# SCH_RFID-design_2024-09-27.net
KiCad netlist of a schematic drawn in EasyEDA
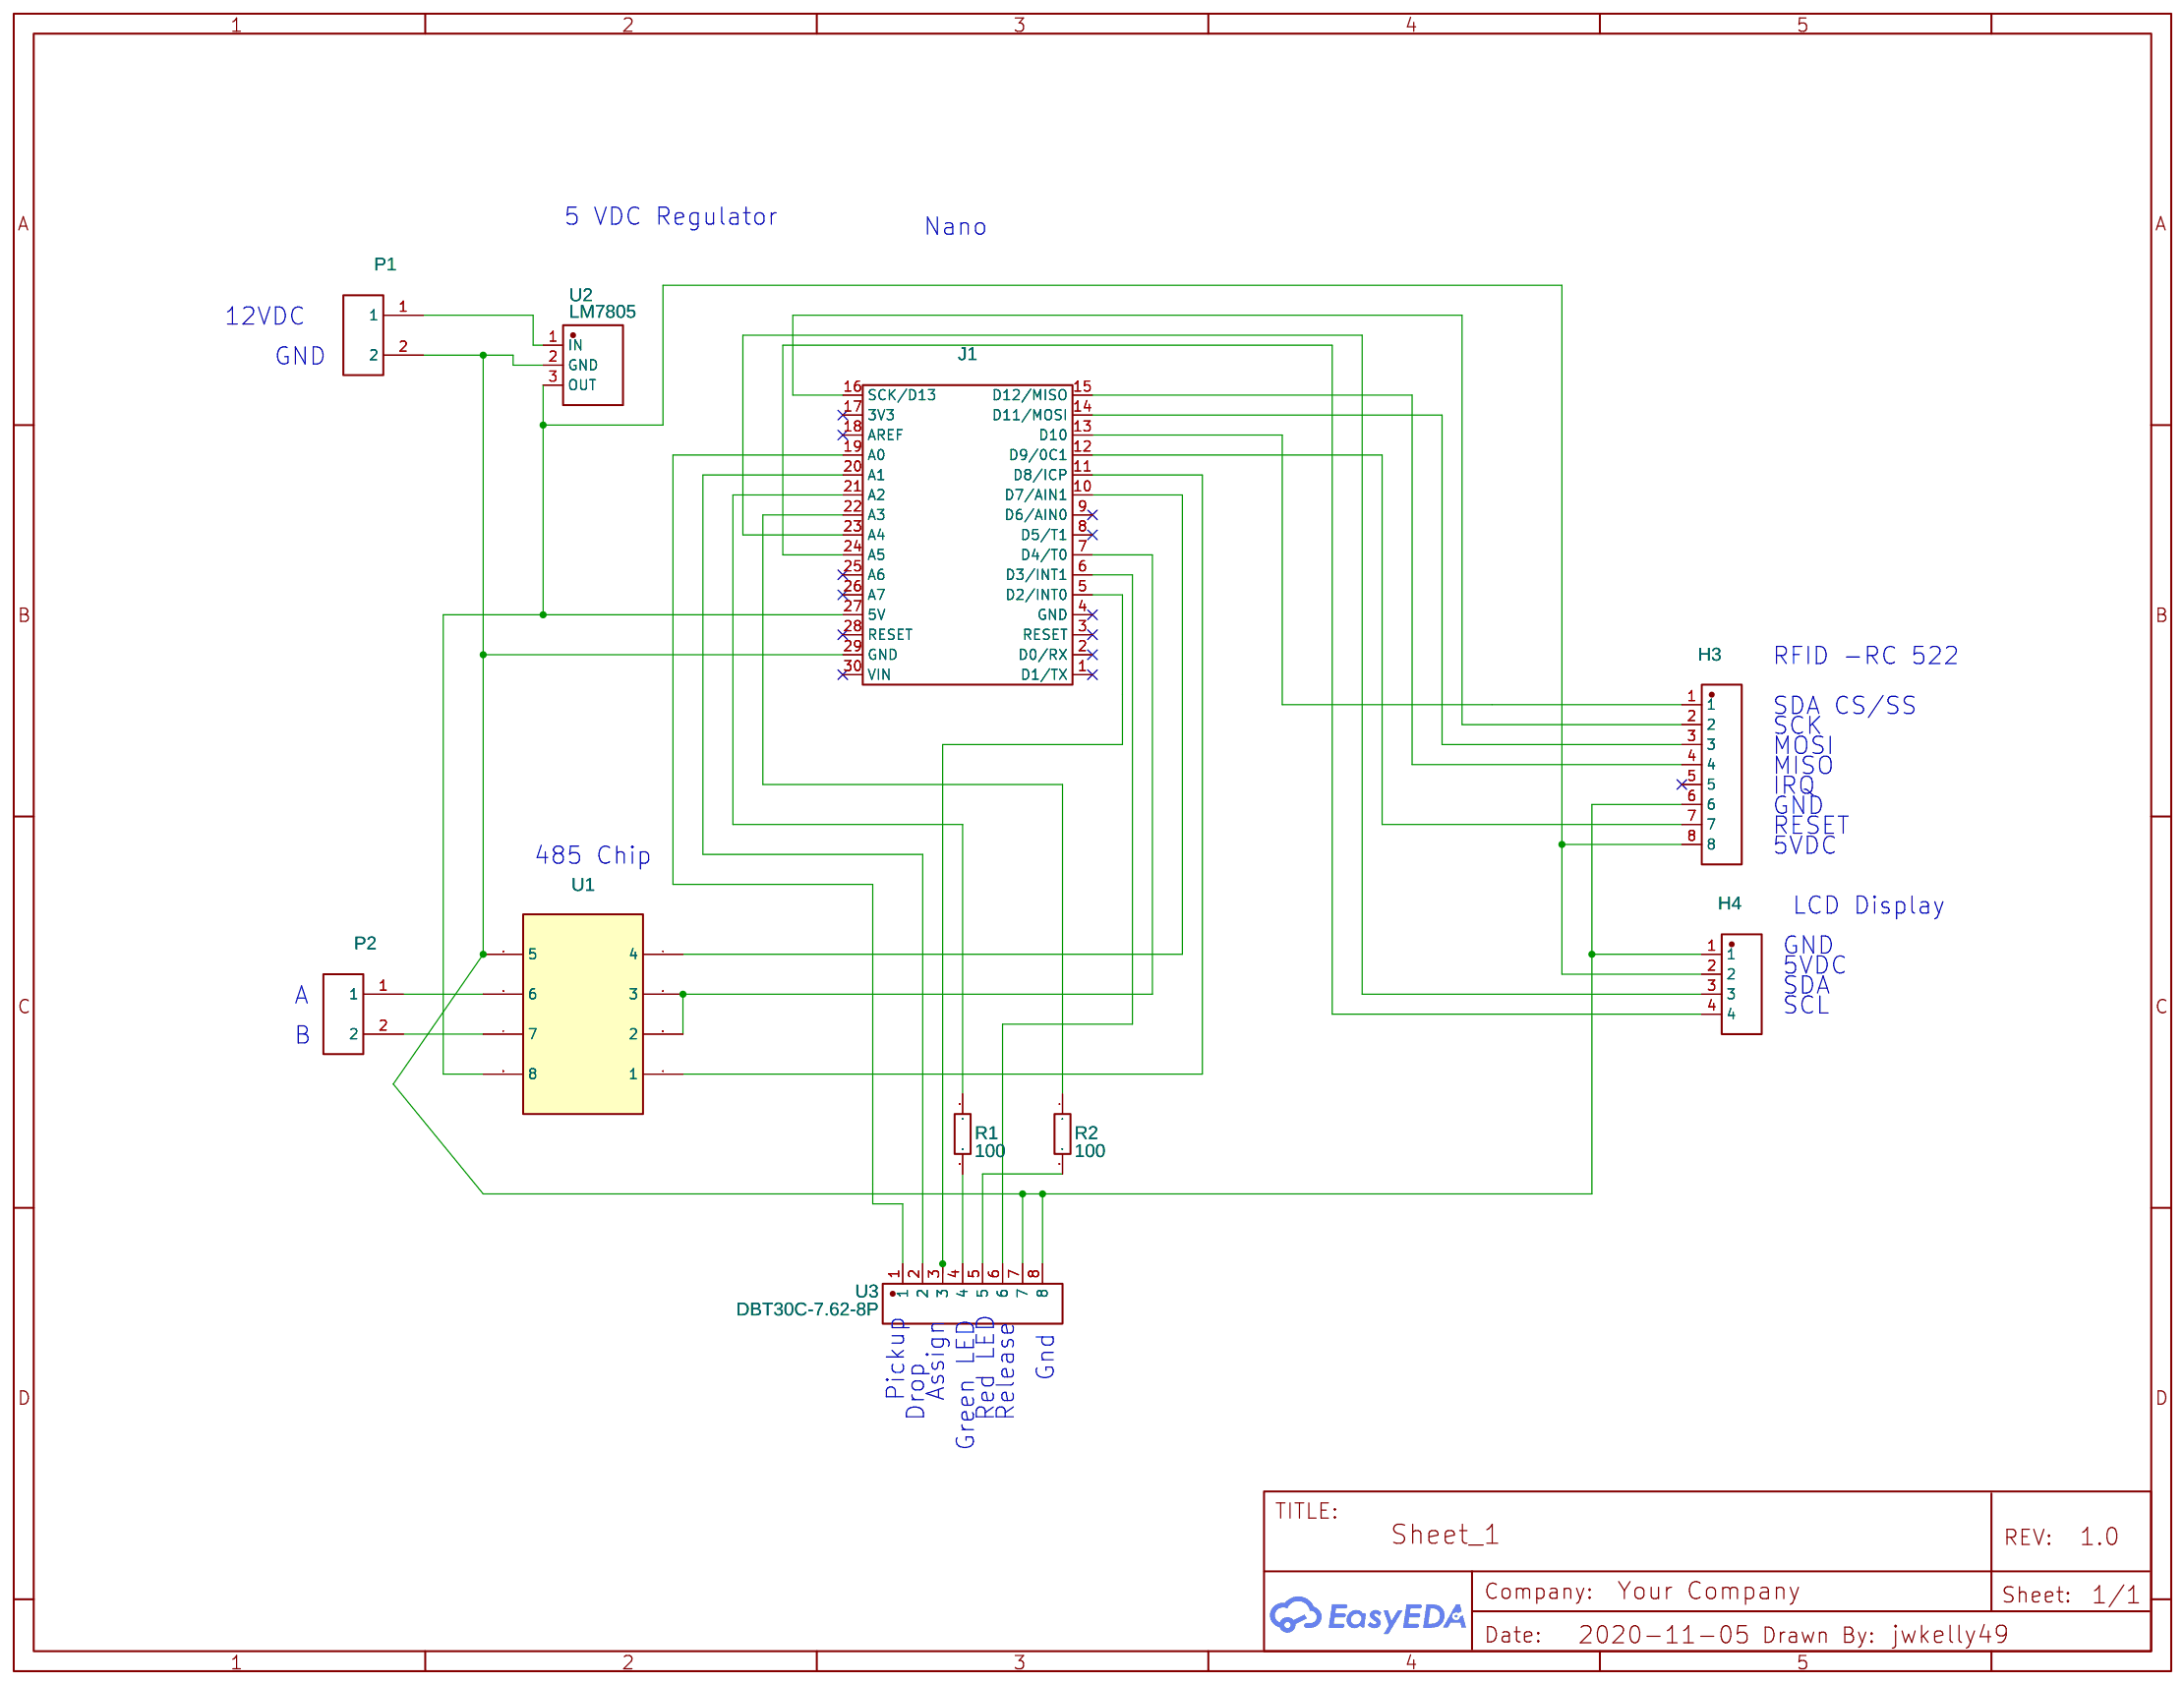
[diagram p0: schematic sheet]

(export (version "E")
  (design (tool "Eeschema 10.0.6"))
  (components
    (comp (ref "H3")
      (value "MTB125-1108R1")
      (fields (field (name "Manufacturer") "MINTRON"))
      (libsource (lib "") (part "MTB125-1108R1"))
    )
    (comp (ref "H4")
      (value "PZ254R-11-04P")
      (fields (field (name "Manufacturer") "XFCN"))
      (libsource (lib "") (part "PZ254R-11-04P"))
    )
    (comp (ref "J1") (value "Arduino_Nano_Header") (libsource (lib "") (part "Unknown_475_-545")))
    (comp (ref "P1")
      (value "WJ45C-B-2P")
      (fields (field (name "Manufacturer") "ReliaPro"))
      (libsource (lib "") (part "WJ45C-B-2P"))
    )
    (comp (ref "P2")
      (value "WJ45C-B-2P")
      (fields (field (name "Manufacturer") "ReliaPro"))
      (libsource (lib "") (part "WJ45C-B-2P"))
    )
    (comp (ref "R1")
      (value "100")
      (fields (field (name "Manufacturer Part") "CFR02SJ0101A10") (field (name "Manufacturer") "UniOhm"))
      (libsource (lib "") (part "CF1/4W-100Ω±5% T52"))
    )
    (comp (ref "R2")
      (value "100")
      (fields (field (name "Manufacturer Part") "CFR02SJ0101A10") (field (name "Manufacturer") "UniOhm"))
      (libsource (lib "") (part "CF1/4W-100Ω±5% T52"))
    )
    (comp (ref "U1")
      (value "DS1009-08AT1NX-0A2")
      (fields (field (name "Manufacturer") "CONNFLY"))
      (libsource (lib "") (part "DS1009-08AT1NX-0A2"))
    )
    (comp (ref "U2")
      (value "LM7805")
      (fields (field (name "Manufacturer") "TF"))
      (libsource (lib "") (part "LM7805"))
    )
    (comp (ref "U3")
      (value "DBT30C-7.62-8P")
      (fields
        (field (name "Manufacturer Part") "DBT30C-7.62-8P-BK-P")
        (field (name "Manufacturer") "DORABO(地博电气)")
      )
      (libsource (lib "") (part "DBT30C-7.62-8P"))
    )
  )
  (nets
    (net (code "1") (name "Net-(J1-5V)") (class "Default")
      (node (ref "H3") (pin "8") (pinfunction "8_8") (pintype "unspecified"))
      (node (ref "H4") (pin "2") (pinfunction "2_2") (pintype "unspecified"))
      (node (ref "J1") (pin "27") (pinfunction "5V_27") (pintype "unspecified"))
      (node (ref "U1") (pin "8") (pinfunction "8_8") (pintype "input"))
      (node (ref "U2") (pin "3") (pinfunction "OUT_3") (pintype "unspecified"))
    )
    (net (code "2") (name "Net-(J1-A0)") (class "Default")
      (node (ref "J1") (pin "19") (pinfunction "A0_19") (pintype "unspecified"))
      (node (ref "U3") (pin "1") (pinfunction "1_1") (pintype "unspecified"))
    )
    (net (code "3") (name "Net-(J1-A1)") (class "Default")
      (node (ref "J1") (pin "20") (pinfunction "A1_20") (pintype "unspecified"))
      (node (ref "U3") (pin "2") (pinfunction "2_2") (pintype "unspecified"))
    )
    (net (code "4") (name "Net-(J1-A2)") (class "Default")
      (node (ref "J1") (pin "21") (pinfunction "A2_21") (pintype "unspecified"))
      (node (ref "R1") (pin "1") (pinfunction "1_1") (pintype "unspecified"))
    )
    (net (code "5") (name "Net-(J1-A3)") (class "Default")
      (node (ref "J1") (pin "22") (pinfunction "A3_22") (pintype "unspecified"))
      (node (ref "R2") (pin "1") (pinfunction "1_1") (pintype "unspecified"))
    )
    (net (code "6") (name "Net-(J1-A4)") (class "Default")
      (node (ref "H4") (pin "3") (pinfunction "3_3") (pintype "unspecified"))
      (node (ref "J1") (pin "23") (pinfunction "A4_23") (pintype "unspecified"))
    )
    (net (code "7") (name "Net-(J1-A5)") (class "Default")
      (node (ref "H4") (pin "4") (pinfunction "4_4") (pintype "unspecified"))
      (node (ref "J1") (pin "24") (pinfunction "A5_24") (pintype "unspecified"))
    )
    (net (code "8") (name "Net-(J1-D2{slash}INT0)") (class "Default")
      (node (ref "J1") (pin "5") (pinfunction "D2/INT0_5") (pintype "unspecified"))
      (node (ref "U3") (pin "3") (pinfunction "3_3") (pintype "unspecified"))
    )
    (net (code "9") (name "Net-(J1-D3{slash}INT1)") (class "Default")
      (node (ref "J1") (pin "6") (pinfunction "D3/INT1_6") (pintype "unspecified"))
      (node (ref "U3") (pin "6") (pinfunction "6_6") (pintype "unspecified"))
    )
    (net (code "10") (name "Net-(J1-D4{slash}T0)") (class "Default")
      (node (ref "J1") (pin "7") (pinfunction "D4/T0_7") (pintype "unspecified"))
      (node (ref "U1") (pin "2") (pinfunction "2_2") (pintype "input"))
      (node (ref "U1") (pin "3") (pinfunction "3_3") (pintype "input"))
    )
    (net (code "11") (name "Net-(J1-D7{slash}AIN1)") (class "Default")
      (node (ref "J1") (pin "10") (pinfunction "D7/AIN1_10") (pintype "unspecified"))
      (node (ref "U1") (pin "4") (pinfunction "4_4") (pintype "input"))
    )
    (net (code "12") (name "Net-(J1-D8{slash}ICP)") (class "Default")
      (node (ref "J1") (pin "11") (pinfunction "D8/ICP_11") (pintype "unspecified"))
      (node (ref "U1") (pin "1") (pinfunction "1_1") (pintype "input"))
    )
    (net (code "13") (name "Net-(J1-D9{slash}0C1)") (class "Default")
      (node (ref "H3") (pin "7") (pinfunction "7_7") (pintype "unspecified"))
      (node (ref "J1") (pin "12") (pinfunction "D9/0C1_12") (pintype "unspecified"))
    )
    (net (code "14") (name "Net-(J1-D10)") (class "Default")
      (node (ref "H3") (pin "1") (pinfunction "1_1") (pintype "unspecified"))
      (node (ref "J1") (pin "13") (pinfunction "D10_13") (pintype "unspecified"))
    )
    (net (code "15") (name "Net-(J1-D11{slash}MOSI)") (class "Default")
      (node (ref "H3") (pin "3") (pinfunction "3_3") (pintype "unspecified"))
      (node (ref "J1") (pin "14") (pinfunction "D11/MOSI_14") (pintype "unspecified"))
    )
    (net (code "16") (name "Net-(J1-D12{slash}MISO)") (class "Default")
      (node (ref "H3") (pin "4") (pinfunction "4_4") (pintype "unspecified"))
      (node (ref "J1") (pin "15") (pinfunction "D12/MISO_15") (pintype "unspecified"))
    )
    (net (code "17") (name "Net-(J1-SCK{slash}D13)") (class "Default")
      (node (ref "H3") (pin "2") (pinfunction "2_2") (pintype "unspecified"))
      (node (ref "J1") (pin "16") (pinfunction "SCK/D13_16") (pintype "unspecified"))
    )
    (net (code "18") (name "Net-(P2-Pad1)") (class "Default")
      (node (ref "P2") (pin "1") (pinfunction "1_1") (pintype "unspecified"))
      (node (ref "U1") (pin "6") (pinfunction "6_6") (pintype "input"))
    )
    (net (code "19") (name "Net-(P2-Pad2)") (class "Default")
      (node (ref "P2") (pin "2") (pinfunction "2_2") (pintype "unspecified"))
      (node (ref "U1") (pin "7") (pinfunction "7_7") (pintype "input"))
    )
    (net (code "20") (name "Net-(R1-Pad2)") (class "Default")
      (node (ref "R1") (pin "2") (pinfunction "2_2") (pintype "unspecified"))
      (node (ref "U3") (pin "4") (pinfunction "4_4") (pintype "unspecified"))
    )
    (net (code "21") (name "Net-(R2-Pad2)") (class "Default")
      (node (ref "R2") (pin "2") (pinfunction "2_2") (pintype "unspecified"))
      (node (ref "U3") (pin "5") (pinfunction "5_5") (pintype "unspecified"))
    )
    (net (code "22") (name "Net-(U2-GND)") (class "Default")
      (node (ref "H3") (pin "6") (pinfunction "6_6") (pintype "unspecified"))
      (node (ref "H4") (pin "1") (pinfunction "1_1") (pintype "unspecified"))
      (node (ref "J1") (pin "29") (pinfunction "GND_29") (pintype "unspecified"))
      (node (ref "P1") (pin "2") (pinfunction "2_2") (pintype "unspecified"))
      (node (ref "U1") (pin "5") (pinfunction "5_5") (pintype "input"))
      (node (ref "U2") (pin "2") (pinfunction "GND_2") (pintype "unspecified"))
      (node (ref "U3") (pin "7") (pinfunction "7_7") (pintype "unspecified"))
      (node (ref "U3") (pin "8") (pinfunction "8_8") (pintype "unspecified"))
    )
    (net (code "23") (name "Net-(U2-IN)") (class "Default")
      (node (ref "P1") (pin "1") (pinfunction "1_1") (pintype "unspecified"))
      (node (ref "U2") (pin "1") (pinfunction "IN_1") (pintype "unspecified"))
    )
    (net (code "24") (name "unconnected-(H3-Pad5)") (class "Default")
      (node (ref "H3") (pin "5") (pinfunction "5_5") (pintype "unspecified+no_connect"))
    )
    (net (code "25") (name "unconnected-(J1-3V3-Pad17)") (class "Default")
      (node (ref "J1") (pin "17") (pinfunction "3V3_17") (pintype "unspecified+no_connect"))
    )
    (net (code "26") (name "unconnected-(J1-A6-Pad25)") (class "Default")
      (node (ref "J1") (pin "25") (pinfunction "A6_25") (pintype "unspecified+no_connect"))
    )
    (net (code "27") (name "unconnected-(J1-A7-Pad26)") (class "Default")
      (node (ref "J1") (pin "26") (pinfunction "A7_26") (pintype "unspecified+no_connect"))
    )
    (net (code "28") (name "unconnected-(J1-AREF-Pad18)") (class "Default")
      (node (ref "J1") (pin "18") (pinfunction "AREF_18") (pintype "unspecified+no_connect"))
    )
    (net (code "29") (name "unconnected-(J1-D0{slash}RX-Pad2)") (class "Default")
      (node (ref "J1") (pin "2") (pinfunction "D0/RX_2") (pintype "unspecified+no_connect"))
    )
    (net (code "30") (name "unconnected-(J1-D1{slash}TX-Pad1)") (class "Default")
      (node (ref "J1") (pin "1") (pinfunction "D1/TX_1") (pintype "unspecified+no_connect"))
    )
    (net (code "31") (name "unconnected-(J1-D5{slash}T1-Pad8)") (class "Default")
      (node (ref "J1") (pin "8") (pinfunction "D5/T1_8") (pintype "unspecified+no_connect"))
    )
    (net (code "32") (name "unconnected-(J1-D6{slash}AIN0-Pad9)") (class "Default")
      (node (ref "J1") (pin "9") (pinfunction "D6/AIN0_9") (pintype "unspecified+no_connect"))
    )
    (net (code "33") (name "unconnected-(J1-GND-Pad4)") (class "Default")
      (node (ref "J1") (pin "4") (pinfunction "GND_4") (pintype "unspecified+no_connect"))
    )
    (net (code "34") (name "unconnected-(J1-RESET-Pad3)") (class "Default")
      (node (ref "J1") (pin "3") (pinfunction "RESET_3") (pintype "unspecified+no_connect"))
    )
    (net (code "35") (name "unconnected-(J1-RESET-Pad28)") (class "Default")
      (node (ref "J1") (pin "28") (pinfunction "RESET_28") (pintype "unspecified+no_connect"))
    )
    (net (code "36") (name "unconnected-(J1-VIN-Pad30)") (class "Default")
      (node (ref "J1") (pin "30") (pinfunction "VIN_30") (pintype "unspecified+no_connect"))
    )
  )
)
